# MCU_-_Power_and_I_O.net
KiCad netlist of a schematic drawn in Altium Designer
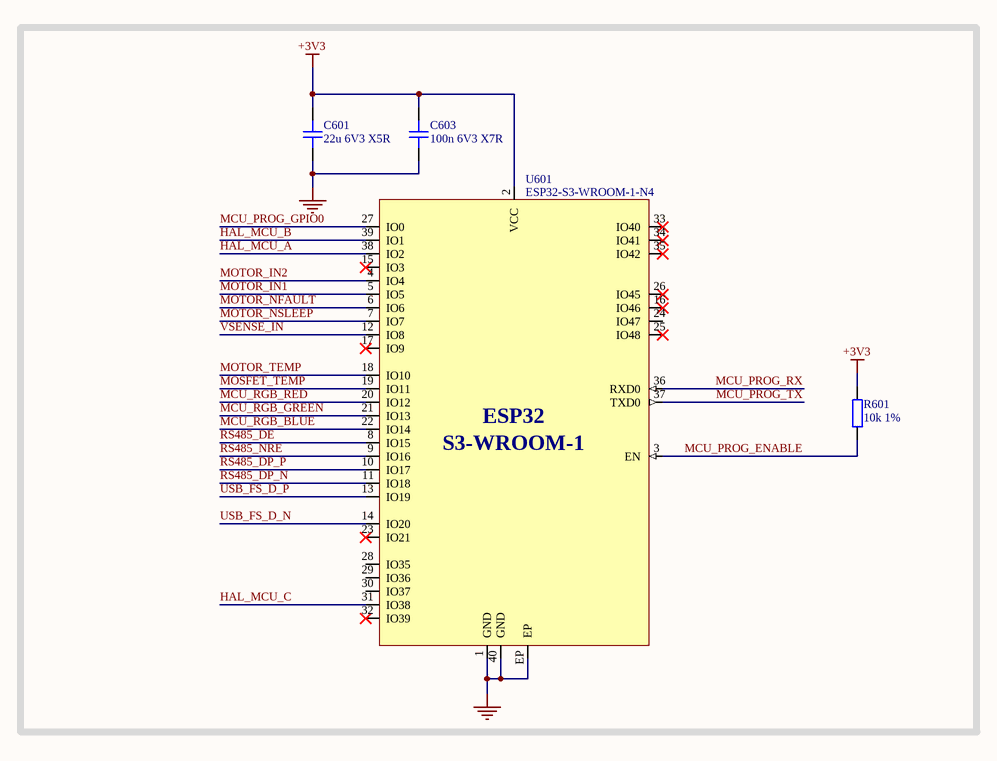
[diagram p0: MCU - Power and I_O.SchDoc]

(export (version "E")
  (design (tool "Eeschema 10.0.6"))
  (components
    (comp (ref "C601")
      (value "22u 6V3 X5R")
      (footprint "CAP_0603")
      (description "Capacitor SMD 0603")
      (fields
        (field (name "MANUFACTURER") "Samsung Electro-Mechanics")
        (field (name "MANUFACTURER PART NUMBER") "CL10A226MQ8NRNC")
      )
      (libsource (lib "Schematic-Lib") (part "CAP_0603"))
    )
    (comp (ref "C603")
      (value "100n 6V3 X7R")
      (footprint "CAP_0402")
      (description "Capacitor SMD 0402")
      (fields
        (field (name "MANUFACTURER") "YAGEO")
        (field (name "MANUFACTURER PART NUMBER") "CC0402KRX7R5BB104")
      )
      (libsource (lib "Schematic-Lib") (part "CAP_0402"))
    )
    (comp (ref "R601")
      (value "10k 1%")
      (footprint "RES_0402")
      (description "Resistor SMD 0402")
      (fields
        (field (name "MANUFACTURER") "PANASONIC")
        (field (name "MANUFACTURER PART NUMBER") "ERJPA2F1002X")
      )
      (libsource (lib "Schematic-Lib-PhilsLab") (part "RES_0402"))
    )
    (comp (ref "U601")
      (value "ESP32-S3-WROOM-1-N4")
      (footprint "ESP32-S3-WROOM-1")
      (fields (field (name "MANUFACTURER") "Espressif"))
      (libsource (lib "Schematic-Lib") (part "ESP32-S3-WROOM-1-N4"))
    )
  )
  (nets
    (net (code "1") (name "+3V3") (class "Default")
      (node (ref "C601") (pin "2") (pinfunction "2_2") (pintype "passive"))
      (node (ref "C603") (pin "2") (pinfunction "2_2") (pintype "passive"))
      (node (ref "R601") (pin "2") (pinfunction "2_2") (pintype "passive"))
      (node (ref "U601") (pin "2") (pinfunction "VCC_2") (pintype "power_in"))
    )
    (net (code "2") (name "/HAL_MCU_A") (class "Default")
      (node (ref "U601") (pin "38") (pinfunction "IO2_38") (pintype "bidirectional"))
    )
    (net (code "3") (name "/HAL_MCU_B") (class "Default")
      (node (ref "U601") (pin "39") (pinfunction "IO1_39") (pintype "bidirectional"))
    )
    (net (code "4") (name "/HAL_MCU_C") (class "Default")
      (node (ref "U601") (pin "31") (pinfunction "IO38_31") (pintype "bidirectional"))
    )
    (net (code "5") (name "/MCU_PROG_ENABLE") (class "Default")
      (node (ref "R601") (pin "1") (pinfunction "1_1") (pintype "passive"))
      (node (ref "U601") (pin "3") (pinfunction "EN_3") (pintype "input"))
    )
    (net (code "6") (name "/MCU_PROG_GPIO0") (class "Default")
      (node (ref "U601") (pin "27") (pinfunction "IO0_27") (pintype "bidirectional"))
    )
    (net (code "7") (name "/MCU_PROG_RX") (class "Default")
      (node (ref "U601") (pin "36") (pinfunction "RXD0_36") (pintype "input"))
    )
    (net (code "8") (name "/MCU_PROG_TX") (class "Default")
      (node (ref "U601") (pin "37") (pinfunction "TXD0_37") (pintype "output"))
    )
    (net (code "9") (name "/MCU_RGB_BLUE") (class "Default")
      (node (ref "U601") (pin "22") (pinfunction "IO14_22") (pintype "bidirectional"))
    )
    (net (code "10") (name "/MCU_RGB_GREEN") (class "Default")
      (node (ref "U601") (pin "21") (pinfunction "IO13_21") (pintype "bidirectional"))
    )
    (net (code "11") (name "/MCU_RGB_RED") (class "Default")
      (node (ref "U601") (pin "20") (pinfunction "IO12_20") (pintype "bidirectional"))
    )
    (net (code "12") (name "/MOSFET_TEMP") (class "Default")
      (node (ref "U601") (pin "19") (pinfunction "IO11_19") (pintype "bidirectional"))
    )
    (net (code "13") (name "/MOTOR_IN1") (class "Default")
      (node (ref "U601") (pin "5") (pinfunction "IO5_5") (pintype "bidirectional"))
    )
    (net (code "14") (name "/MOTOR_IN2") (class "Default")
      (node (ref "U601") (pin "4") (pinfunction "IO4_4") (pintype "bidirectional"))
    )
    (net (code "15") (name "/MOTOR_NFAULT") (class "Default")
      (node (ref "U601") (pin "6") (pinfunction "IO6_6") (pintype "bidirectional"))
    )
    (net (code "16") (name "/MOTOR_NSLEEP") (class "Default")
      (node (ref "U601") (pin "7") (pinfunction "IO7_7") (pintype "bidirectional"))
    )
    (net (code "17") (name "/MOTOR_TEMP") (class "Default")
      (node (ref "U601") (pin "18") (pinfunction "IO10_18") (pintype "bidirectional"))
    )
    (net (code "18") (name "/RS485_DE") (class "Default")
      (node (ref "U601") (pin "8") (pinfunction "IO15_8") (pintype "bidirectional"))
    )
    (net (code "19") (name "/RS485_DP_N") (class "Default")
      (node (ref "U601") (pin "11") (pinfunction "IO18_11") (pintype "bidirectional"))
    )
    (net (code "20") (name "/RS485_DP_P") (class "Default")
      (node (ref "U601") (pin "10") (pinfunction "IO17_10") (pintype "bidirectional"))
    )
    (net (code "21") (name "/RS485_NRE") (class "Default")
      (node (ref "U601") (pin "9") (pinfunction "IO16_9") (pintype "bidirectional"))
    )
    (net (code "22") (name "/USB_FS_D_N") (class "Default")
      (node (ref "U601") (pin "14") (pinfunction "IO20_14") (pintype "bidirectional"))
    )
    (net (code "23") (name "/USB_FS_D_P") (class "Default")
      (node (ref "U601") (pin "13") (pinfunction "IO19_13") (pintype "bidirectional"))
    )
    (net (code "24") (name "/VSENSE_IN") (class "Default")
      (node (ref "U601") (pin "12") (pinfunction "IO8_12") (pintype "bidirectional"))
    )
    (net (code "25") (name "GND") (class "Default")
      (node (ref "C601") (pin "1") (pinfunction "1_1") (pintype "passive"))
      (node (ref "C603") (pin "1") (pinfunction "1_1") (pintype "passive"))
      (node (ref "U601") (pin "1") (pinfunction "GND_1") (pintype "power_in"))
      (node (ref "U601") (pin "40") (pinfunction "GND_40") (pintype "power_in"))
      (node (ref "U601") (pin "EP") (pinfunction "EP_EP") (pintype "power_in"))
    )
    (net (code "26") (name "unconnected-(U601-IO3-Pad15)") (class "Default")
      (node (ref "U601") (pin "15") (pinfunction "IO3_15") (pintype "bidirectional+no_connect"))
    )
    (net (code "27") (name "unconnected-(U601-IO9-Pad17)") (class "Default")
      (node (ref "U601") (pin "17") (pinfunction "IO9_17") (pintype "bidirectional+no_connect"))
    )
    (net (code "28") (name "unconnected-(U601-IO21-Pad23)") (class "Default")
      (node (ref "U601") (pin "23") (pinfunction "IO21_23") (pintype "bidirectional+no_connect"))
    )
    (net (code "29") (name "unconnected-(U601-IO35-Pad28)") (class "Default")
      (node (ref "U601") (pin "28") (pinfunction "IO35_28") (pintype "bidirectional"))
    )
    (net (code "30") (name "unconnected-(U601-IO36-Pad29)") (class "Default")
      (node (ref "U601") (pin "29") (pinfunction "IO36_29") (pintype "bidirectional"))
    )
    (net (code "31") (name "unconnected-(U601-IO37-Pad30)") (class "Default")
      (node (ref "U601") (pin "30") (pinfunction "IO37_30") (pintype "bidirectional"))
    )
    (net (code "32") (name "unconnected-(U601-IO39-Pad32)") (class "Default")
      (node (ref "U601") (pin "32") (pinfunction "IO39_32") (pintype "bidirectional+no_connect"))
    )
    (net (code "33") (name "unconnected-(U601-IO40-Pad33)") (class "Default")
      (node (ref "U601") (pin "33") (pinfunction "IO40_33") (pintype "bidirectional+no_connect"))
    )
    (net (code "34") (name "unconnected-(U601-IO41-Pad34)") (class "Default")
      (node (ref "U601") (pin "34") (pinfunction "IO41_34") (pintype "bidirectional+no_connect"))
    )
    (net (code "35") (name "unconnected-(U601-IO42-Pad35)") (class "Default")
      (node (ref "U601") (pin "35") (pinfunction "IO42_35") (pintype "bidirectional+no_connect"))
    )
    (net (code "36") (name "unconnected-(U601-IO45-Pad26)") (class "Default")
      (node (ref "U601") (pin "26") (pinfunction "IO45_26") (pintype "bidirectional+no_connect"))
    )
    (net (code "37") (name "unconnected-(U601-IO46-Pad16)") (class "Default")
      (node (ref "U601") (pin "16") (pinfunction "IO46_16") (pintype "bidirectional+no_connect"))
    )
    (net (code "38") (name "unconnected-(U601-IO47-Pad24)") (class "Default")
      (node (ref "U601") (pin "24") (pinfunction "IO47_24") (pintype "bidirectional"))
    )
    (net (code "39") (name "unconnected-(U601-IO48-Pad25)") (class "Default")
      (node (ref "U601") (pin "25") (pinfunction "IO48_25") (pintype "bidirectional+no_connect"))
    )
  )
)
